# rps.net
KiCad netlist of a schematic drawn in EAGLE
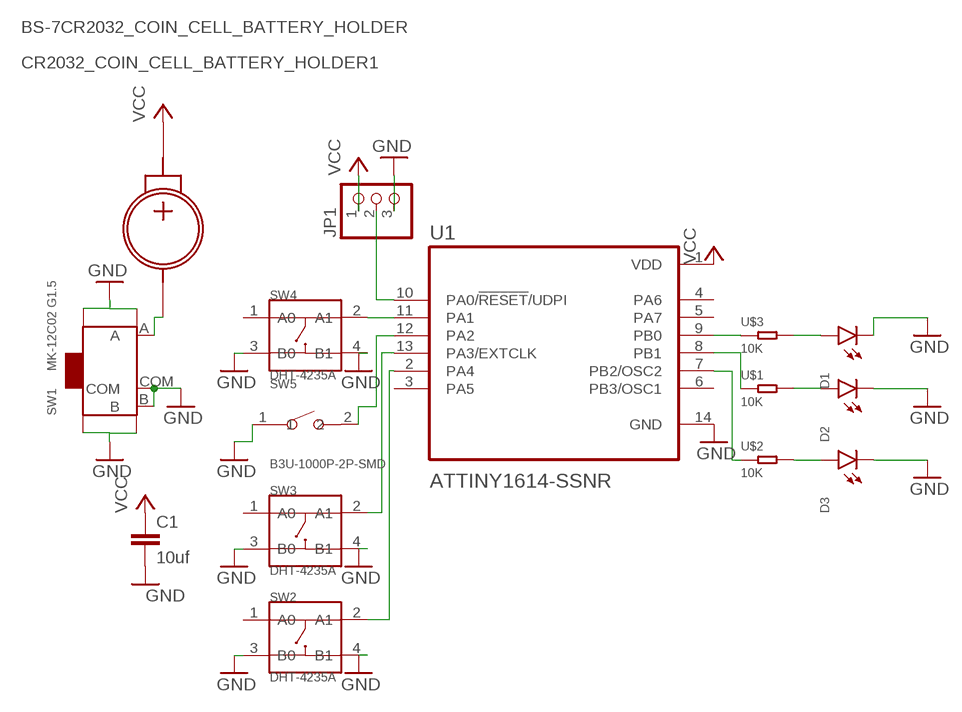
[diagram p0: schematic, sheet 1]

(export (version "E")
  (design (tool "Eeschema 10.0.6"))
  (components
    (comp (ref "C1")
      (value "10uf")
      (footprint "eagle-import:C0805")
      (libsource (lib "eagle-import") (part "C-EUC0805"))
    )
    (comp (ref "CR2032_COIN_CELL_BATTERY_HOLDER1")
      (value "BS-7CR2032_COIN_CELL_BATTERY_HOLDER")
      (footprint "eagle-import:BS-7")
      (fields (field (name "MF") "MPD") (field (name "MP") "BS-7"))
      (libsource (lib "eagle-import") (part "BS-7CR2032_COIN_CELL_BATTERY_HOLDER"))
    )
    (comp (ref "D1")
      (value "YELLOW-0805")
      (footprint "eagle-import:SML0805")
      (libsource (lib "eagle-import") (part "LEDSML0805"))
    )
    (comp (ref "D2")
      (value "YELLOW-0805")
      (footprint "eagle-import:SML0805")
      (libsource (lib "eagle-import") (part "LEDSML0805"))
    )
    (comp (ref "D3")
      (value "YELLOW-0805")
      (footprint "eagle-import:SML0805")
      (libsource (lib "eagle-import") (part "LEDSML0805"))
    )
    (comp (ref "JP1")
      (value "PINHD-1X3")
      (footprint "eagle-import:1X03")
      (libsource (lib "eagle-import") (part "PINHD-1X3"))
    )
    (comp (ref "SW1")
      (value "MK-12C02 G1.5")
      (footprint "eagle-import:SW7-SMD-L6.7X2.7X3.2MM")
      (libsource (lib "eagle-import") (part "SMD-TOGGLE-SWITCH-ON-ON(3+4P-6.7X2.7MM)"))
    )
    (comp (ref "SW2")
      (value "DHT-4235A")
      (footprint "eagle-import:SW4-SMD-4.2X3.2X2.5MM")
      (libsource (lib "eagle-import") (part "SMD-BUTTON-TOP-DHT-4235A(4P-4.2X3.2MM)"))
    )
    (comp (ref "SW3")
      (value "DHT-4235A")
      (footprint "eagle-import:SW4-SMD-4.2X3.2X2.5MM")
      (libsource (lib "eagle-import") (part "SMD-BUTTON-TOP-DHT-4235A(4P-4.2X3.2MM)"))
    )
    (comp (ref "SW4")
      (value "DHT-4235A")
      (footprint "eagle-import:SW4-SMD-4.2X3.2X2.5MM")
      (libsource (lib "eagle-import") (part "SMD-BUTTON-TOP-DHT-4235A(4P-4.2X3.2MM)"))
    )
    (comp (ref "SW5")
      (value "B3U-1000P-2P-SMD")
      (footprint "eagle-import:SW2-2.6-3.0X2.5X1.2+0.4MM")
      (libsource (lib "eagle-import") (part "SMD-BUTTON(2P-3.0X2.5X1.2+0.4MM)-B3U-1000P-2P-SMD"))
    )
    (comp (ref "U$1")
      (value "10K")
      (footprint "eagle-import:R0805")
      (fields (field (name "MPN") "RC0805FR-0710KL"))
      (libsource (lib "eagle-import") (part "SMD-RES-10K-1%-1/8W(0805)"))
    )
    (comp (ref "U$2")
      (value "10K")
      (footprint "eagle-import:R0805")
      (fields (field (name "MPN") "RC0805FR-0710KL"))
      (libsource (lib "eagle-import") (part "SMD-RES-10K-1%-1/8W(0805)"))
    )
    (comp (ref "U$3")
      (value "10K")
      (footprint "eagle-import:R0805")
      (fields (field (name "MPN") "RC0805FR-0710KL"))
      (libsource (lib "eagle-import") (part "SMD-RES-10K-1%-1/8W(0805)"))
    )
    (comp (ref "U1")
      (value "ATTINY1614-SSNR")
      (footprint "eagle-import:SOIC127P600X175-14N")
      (fields (field (name "MF") "Microchip"))
      (libsource (lib "eagle-import") (part "ATTINY1614-SSNR"))
    )
  )
  (nets
    (net (code "1") (name "GND") (class "Default")
      (node (ref "C1") (pin "2") (pinfunction "2_2") (pintype "passive"))
      (node (ref "D1") (pin "C") (pinfunction "C_C") (pintype "passive"))
      (node (ref "D2") (pin "C") (pinfunction "C_C") (pintype "passive"))
      (node (ref "D3") (pin "C") (pinfunction "C_C") (pintype "passive"))
      (node (ref "JP1") (pin "3") (pinfunction "3_3") (pintype "passive"))
      (node (ref "SW1") (pin "B") (pinfunction "B_B") (pintype "bidirectional"))
      (node (ref "SW1") (pin "COM") (pinfunction "COM_COM") (pintype "bidirectional"))
      (node (ref "SW1") (pin "SS1") (pinfunction "SS1_SS1") (pintype "bidirectional"))
      (node (ref "SW1") (pin "SS2") (pinfunction "SS2_SS2") (pintype "bidirectional"))
      (node (ref "SW1") (pin "SS3") (pinfunction "SS3_SS3") (pintype "bidirectional"))
      (node (ref "SW1") (pin "SS4") (pinfunction "SS4_SS4") (pintype "bidirectional"))
      (node (ref "SW2") (pin "3") (pinfunction "B0_3") (pintype "bidirectional"))
      (node (ref "SW2") (pin "4") (pinfunction "B1_4") (pintype "bidirectional"))
      (node (ref "SW3") (pin "3") (pinfunction "B0_3") (pintype "bidirectional"))
      (node (ref "SW3") (pin "4") (pinfunction "B1_4") (pintype "bidirectional"))
      (node (ref "SW4") (pin "3") (pinfunction "B0_3") (pintype "bidirectional"))
      (node (ref "SW4") (pin "4") (pinfunction "B1_4") (pintype "bidirectional"))
      (node (ref "SW5") (pin "1") (pinfunction "1_1") (pintype "bidirectional"))
      (node (ref "U1") (pin "14") (pinfunction "GND_14") (pintype "power_in"))
    )
    (net (code "2") (name "Net-(CR2032_COIN_CELL_BATTERY_HOLDER1-PadNEG)") (class "Default")
      (node (ref "CR2032_COIN_CELL_BATTERY_HOLDER1") (pin "NEG") (pinfunction "NEG_NEG") (pintype "power_in"))
      (node (ref "SW1") (pin "A") (pinfunction "A_A") (pintype "bidirectional"))
    )
    (net (code "3") (name "Net-(D1-PadA)") (class "Default")
      (node (ref "D1") (pin "A") (pinfunction "A_A") (pintype "passive"))
      (node (ref "U$3") (pin "2") (pinfunction "2_2") (pintype "passive"))
    )
    (net (code "4") (name "Net-(D2-PadA)") (class "Default")
      (node (ref "D2") (pin "A") (pinfunction "A_A") (pintype "passive"))
      (node (ref "U$1") (pin "2") (pinfunction "2_2") (pintype "passive"))
    )
    (net (code "5") (name "Net-(D3-PadA)") (class "Default")
      (node (ref "D3") (pin "A") (pinfunction "A_A") (pintype "passive"))
      (node (ref "U$2") (pin "2") (pinfunction "2_2") (pintype "passive"))
    )
    (net (code "6") (name "Net-(SW2-A1)") (class "Default")
      (node (ref "SW2") (pin "2") (pinfunction "A1_2") (pintype "bidirectional"))
      (node (ref "U1") (pin "2") (pinfunction "PA4_2") (pintype "bidirectional"))
    )
    (net (code "7") (name "Net-(SW3-A1)") (class "Default")
      (node (ref "SW3") (pin "2") (pinfunction "A1_2") (pintype "bidirectional"))
      (node (ref "U1") (pin "13") (pinfunction "PA3/EXTCLK_13") (pintype "bidirectional"))
    )
    (net (code "8") (name "Net-(SW4-A1)") (class "Default")
      (node (ref "SW4") (pin "2") (pinfunction "A1_2") (pintype "bidirectional"))
      (node (ref "U1") (pin "11") (pinfunction "PA1_11") (pintype "bidirectional"))
    )
    (net (code "9") (name "Net-(U1-PA0{slash}~{RESET}{slash}UDPI)") (class "Default")
      (node (ref "JP1") (pin "2") (pinfunction "2_2") (pintype "passive"))
      (node (ref "U1") (pin "10") (pinfunction "PA0/~{RESET}/UDPI_10") (pintype "bidirectional"))
    )
    (net (code "10") (name "Net-(U1-PA2)") (class "Default")
      (node (ref "SW5") (pin "2") (pinfunction "2_2") (pintype "bidirectional"))
      (node (ref "U1") (pin "12") (pinfunction "PA2_12") (pintype "bidirectional"))
    )
    (net (code "11") (name "Net-(U1-PB0)") (class "Default")
      (node (ref "U$3") (pin "1") (pinfunction "1_1") (pintype "passive"))
      (node (ref "U1") (pin "9") (pinfunction "PB0_9") (pintype "bidirectional"))
    )
    (net (code "12") (name "Net-(U1-PB1)") (class "Default")
      (node (ref "U$1") (pin "1") (pinfunction "1_1") (pintype "passive"))
      (node (ref "U1") (pin "8") (pinfunction "PB1_8") (pintype "bidirectional"))
    )
    (net (code "13") (name "Net-(U1-PB2{slash}OSC2)") (class "Default")
      (node (ref "U$2") (pin "1") (pinfunction "1_1") (pintype "passive"))
      (node (ref "U1") (pin "7") (pinfunction "PB2/OSC2_7") (pintype "bidirectional"))
    )
    (net (code "14") (name "VCC") (class "Default")
      (node (ref "C1") (pin "1") (pinfunction "1_1") (pintype "passive"))
      (node (ref "CR2032_COIN_CELL_BATTERY_HOLDER1") (pin "POS") (pinfunction "POS_POS") (pintype "power_in"))
      (node (ref "JP1") (pin "1") (pinfunction "1_1") (pintype "passive"))
      (node (ref "U1") (pin "1") (pinfunction "VDD_1") (pintype "power_in"))
    )
    (net (code "15") (name "unconnected-(SW2-A0-Pad1)") (class "Default")
      (node (ref "SW2") (pin "1") (pinfunction "A0_1") (pintype "bidirectional"))
    )
    (net (code "16") (name "unconnected-(SW3-A0-Pad1)") (class "Default")
      (node (ref "SW3") (pin "1") (pinfunction "A0_1") (pintype "bidirectional"))
    )
    (net (code "17") (name "unconnected-(SW4-A0-Pad1)") (class "Default")
      (node (ref "SW4") (pin "1") (pinfunction "A0_1") (pintype "bidirectional"))
    )
    (net (code "18") (name "unconnected-(U1-PA5-Pad3)") (class "Default")
      (node (ref "U1") (pin "3") (pinfunction "PA5_3") (pintype "bidirectional"))
    )
    (net (code "19") (name "unconnected-(U1-PA6-Pad4)") (class "Default")
      (node (ref "U1") (pin "4") (pinfunction "PA6_4") (pintype "bidirectional"))
    )
    (net (code "20") (name "unconnected-(U1-PA7-Pad5)") (class "Default")
      (node (ref "U1") (pin "5") (pinfunction "PA7_5") (pintype "bidirectional"))
    )
    (net (code "21") (name "unconnected-(U1-PB3{slash}OSC1-Pad6)") (class "Default")
      (node (ref "U1") (pin "6") (pinfunction "PB3/OSC1_6") (pintype "bidirectional"))
    )
  )
)
